# akabeacon_circle_MDBT40_type2.net
KiCad netlist of a schematic drawn in EAGLE
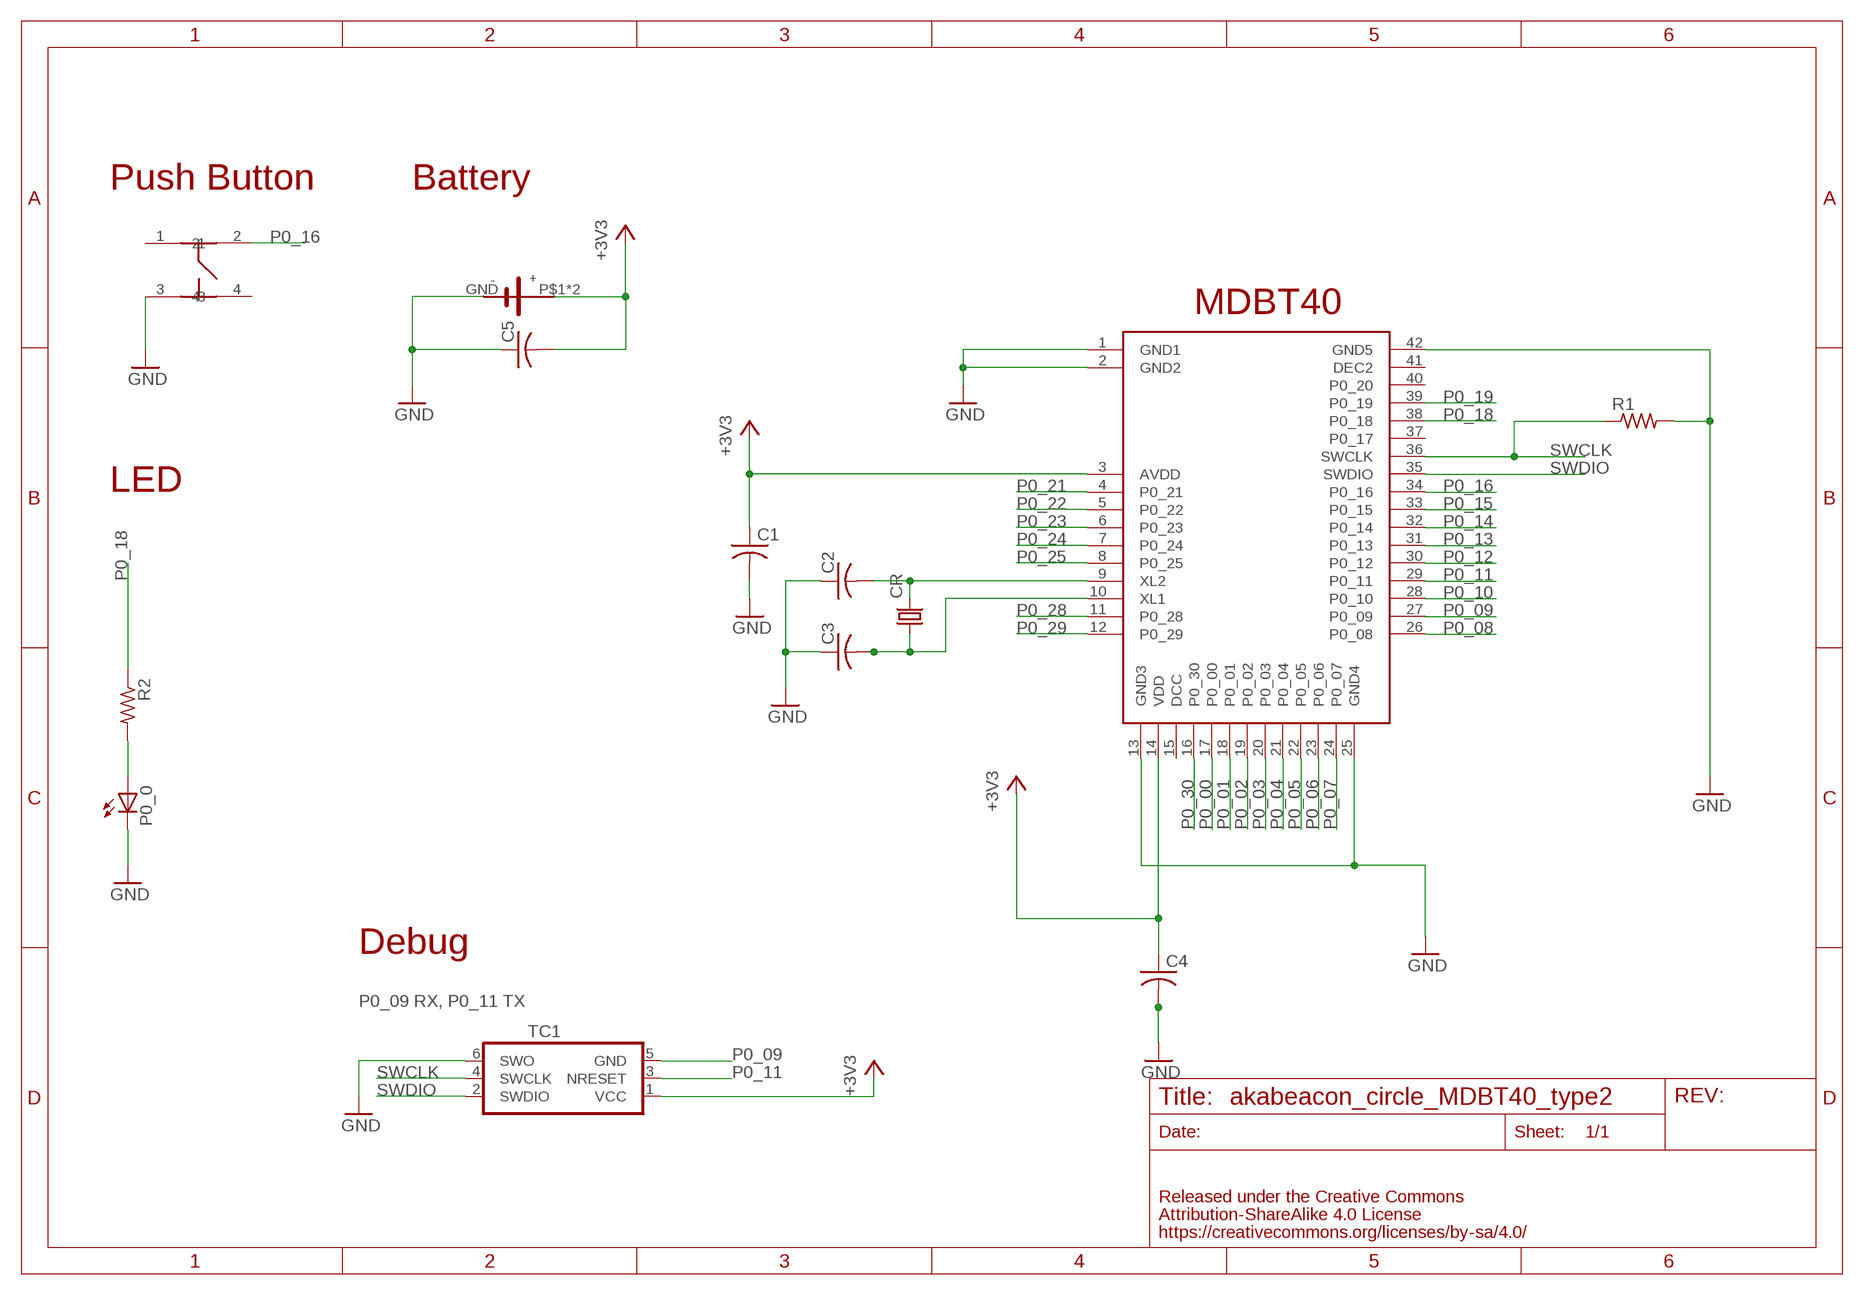
[diagram p0: schematic, sheet 1]

(export (version "E")
  (design (tool "Eeschema 10.0.6"))
  (components
    (comp (ref "C1")
      (value "C-USC0603")
      (footprint "eagle-import:C0603")
      (libsource (lib "eagle-import") (part "C-USC0603"))
    )
    (comp (ref "C2")
      (value "C-USC0603")
      (footprint "eagle-import:C0603")
      (libsource (lib "eagle-import") (part "C-USC0603"))
    )
    (comp (ref "C3")
      (value "C-USC0603")
      (footprint "eagle-import:C0603")
      (libsource (lib "eagle-import") (part "C-USC0603"))
    )
    (comp (ref "C4")
      (value "C-USC0603")
      (footprint "eagle-import:C0603")
      (libsource (lib "eagle-import") (part "C-USC0603"))
    )
    (comp (ref "C5")
      (value "C-USC0603")
      (footprint "eagle-import:C0603")
      (libsource (lib "eagle-import") (part "C-USC0603"))
    )
    (comp (ref "CR")
      (value "FC-12M")
      (footprint "eagle-import:FC-12M")
      (libsource (lib "eagle-import") (part "FC-12M"))
    )
    (comp (ref "P0_0")
      (value "LEDCHIP-LED0603")
      (footprint "eagle-import:CHIP-LED0603")
      (libsource (lib "eagle-import") (part "LEDCHIP-LED0603"))
    )
    (comp (ref "R1")
      (value "R-US_R0603")
      (footprint "eagle-import:R0603")
      (libsource (lib "eagle-import") (part "R-US_R0603"))
    )
    (comp (ref "R2")
      (value "R-US_R0603")
      (footprint "eagle-import:R0603")
      (libsource (lib "eagle-import") (part "R-US_R0603"))
    )
    (comp (ref "TC1")
      (value "TC2030-IDC-NL")
      (footprint "eagle-import:TC2030-IDC-NL")
      (libsource (lib "eagle-import") (part "TC2030-IDC-NL"))
    )
    (comp (ref "U$1")
      (value "RAYTAC-MDBT40")
      (footprint "eagle-import:RAYTAC-MDBT40")
      (libsource (lib "eagle-import") (part "RAYTAC-MDBT40"))
    )
    (comp (ref "U$3")
      (value "CIRCLE-TYPE2")
      (footprint "eagle-import:CIRCLE-TYPE2-TC2030")
      (libsource (lib "eagle-import") (part "CIRCLE-TYPE2"))
    )
    (comp (ref "U$5")
      (value "SWICTH-4P(KMR2)")
      (footprint "eagle-import:SWITCH-4P(KMR2)")
      (libsource (lib "eagle-import") (part "SWICTH-4P(KMR2)"))
    )
  )
  (nets
    (net (code "1") (name "+3V3") (class "Default")
      (node (ref "C1") (pin "1") (pinfunction "1_1") (pintype "passive"))
      (node (ref "C4") (pin "1") (pinfunction "1_1") (pintype "passive"))
      (node (ref "C5") (pin "2") (pinfunction "2_2") (pintype "passive"))
      (node (ref "TC1") (pin "1") (pinfunction "VCC_1") (pintype "passive"))
      (node (ref "U$1") (pin "14") (pinfunction "VDD_14") (pintype "bidirectional"))
      (node (ref "U$1") (pin "3") (pinfunction "AVDD_3") (pintype "bidirectional"))
      (node (ref "U$3") (pin "P$1") (pinfunction "VCC_P$1") (pintype "bidirectional"))
      (node (ref "U$3") (pin "P$2") (pinfunction "VCC_P$2") (pintype "bidirectional"))
    )
    (net (code "2") (name "/P0_00") (class "Default")
      (node (ref "U$1") (pin "17") (pinfunction "P0_00_17") (pintype "bidirectional"))
    )
    (net (code "3") (name "/P0_01") (class "Default")
      (node (ref "U$1") (pin "18") (pinfunction "P0_01_18") (pintype "bidirectional"))
    )
    (net (code "4") (name "/P0_02") (class "Default")
      (node (ref "U$1") (pin "19") (pinfunction "P0_02_19") (pintype "bidirectional"))
    )
    (net (code "5") (name "/P0_03") (class "Default")
      (node (ref "U$1") (pin "20") (pinfunction "P0_03_20") (pintype "bidirectional"))
    )
    (net (code "6") (name "/P0_04") (class "Default")
      (node (ref "U$1") (pin "21") (pinfunction "P0_04_21") (pintype "bidirectional"))
    )
    (net (code "7") (name "/P0_05") (class "Default")
      (node (ref "U$1") (pin "22") (pinfunction "P0_05_22") (pintype "bidirectional"))
    )
    (net (code "8") (name "/P0_06") (class "Default")
      (node (ref "U$1") (pin "23") (pinfunction "P0_06_23") (pintype "bidirectional"))
    )
    (net (code "9") (name "/P0_07") (class "Default")
      (node (ref "U$1") (pin "24") (pinfunction "P0_07_24") (pintype "bidirectional"))
    )
    (net (code "10") (name "/P0_08") (class "Default")
      (node (ref "U$1") (pin "26") (pinfunction "P0_08_26") (pintype "bidirectional"))
    )
    (net (code "11") (name "/P0_09") (class "Default")
      (node (ref "TC1") (pin "5") (pinfunction "GND_5") (pintype "passive"))
      (node (ref "U$1") (pin "27") (pinfunction "P0_09_27") (pintype "bidirectional"))
    )
    (net (code "12") (name "/P0_10") (class "Default")
      (node (ref "U$1") (pin "28") (pinfunction "P0_10_28") (pintype "bidirectional"))
    )
    (net (code "13") (name "/P0_11") (class "Default")
      (node (ref "TC1") (pin "3") (pinfunction "NRESET_3") (pintype "passive"))
      (node (ref "U$1") (pin "29") (pinfunction "P0_11_29") (pintype "bidirectional"))
    )
    (net (code "14") (name "/P0_12") (class "Default")
      (node (ref "U$1") (pin "30") (pinfunction "P0_12_30") (pintype "bidirectional"))
    )
    (net (code "15") (name "/P0_13") (class "Default")
      (node (ref "U$1") (pin "31") (pinfunction "P0_13_31") (pintype "bidirectional"))
    )
    (net (code "16") (name "/P0_14") (class "Default")
      (node (ref "U$1") (pin "32") (pinfunction "P0_14_32") (pintype "bidirectional"))
    )
    (net (code "17") (name "/P0_15") (class "Default")
      (node (ref "U$1") (pin "33") (pinfunction "P0_15_33") (pintype "bidirectional"))
    )
    (net (code "18") (name "/P0_16") (class "Default")
      (node (ref "U$1") (pin "34") (pinfunction "P0_16_34") (pintype "bidirectional"))
      (node (ref "U$5") (pin "2") (pinfunction "2_2") (pintype "bidirectional"))
    )
    (net (code "19") (name "/P0_18") (class "Default")
      (node (ref "R2") (pin "1") (pinfunction "1_1") (pintype "passive"))
      (node (ref "U$1") (pin "38") (pinfunction "P0_18_38") (pintype "bidirectional"))
    )
    (net (code "20") (name "/P0_19") (class "Default")
      (node (ref "U$1") (pin "39") (pinfunction "P0_19_39") (pintype "bidirectional"))
    )
    (net (code "21") (name "/P0_21") (class "Default")
      (node (ref "U$1") (pin "4") (pinfunction "P0_21_4") (pintype "bidirectional"))
    )
    (net (code "22") (name "/P0_22") (class "Default")
      (node (ref "U$1") (pin "5") (pinfunction "P0_22_5") (pintype "bidirectional"))
    )
    (net (code "23") (name "/P0_23") (class "Default")
      (node (ref "U$1") (pin "6") (pinfunction "P0_23_6") (pintype "bidirectional"))
    )
    (net (code "24") (name "/P0_24") (class "Default")
      (node (ref "U$1") (pin "7") (pinfunction "P0_24_7") (pintype "bidirectional"))
    )
    (net (code "25") (name "/P0_25") (class "Default")
      (node (ref "U$1") (pin "8") (pinfunction "P0_25_8") (pintype "bidirectional"))
    )
    (net (code "26") (name "/P0_28") (class "Default")
      (node (ref "U$1") (pin "11") (pinfunction "P0_28_11") (pintype "bidirectional"))
    )
    (net (code "27") (name "/P0_29") (class "Default")
      (node (ref "U$1") (pin "12") (pinfunction "P0_29_12") (pintype "bidirectional"))
    )
    (net (code "28") (name "/P0_30") (class "Default")
      (node (ref "U$1") (pin "16") (pinfunction "P0_30_16") (pintype "bidirectional"))
    )
    (net (code "29") (name "/SWCLK") (class "Default")
      (node (ref "R1") (pin "1") (pinfunction "1_1") (pintype "passive"))
      (node (ref "TC1") (pin "4") (pinfunction "SWCLK_4") (pintype "passive"))
      (node (ref "U$1") (pin "36") (pinfunction "SWCLK_36") (pintype "bidirectional"))
    )
    (net (code "30") (name "/SWDIO") (class "Default")
      (node (ref "TC1") (pin "2") (pinfunction "SWDIO_2") (pintype "passive"))
      (node (ref "U$1") (pin "35") (pinfunction "SWDIO_35") (pintype "bidirectional"))
    )
    (net (code "31") (name "GND") (class "Default")
      (node (ref "C1") (pin "2") (pinfunction "2_2") (pintype "passive"))
      (node (ref "C2") (pin "1") (pinfunction "1_1") (pintype "passive"))
      (node (ref "C3") (pin "1") (pinfunction "1_1") (pintype "passive"))
      (node (ref "C4") (pin "2") (pinfunction "2_2") (pintype "passive"))
      (node (ref "C5") (pin "1") (pinfunction "1_1") (pintype "passive"))
      (node (ref "P0_0") (pin "C") (pinfunction "C_C") (pintype "passive"))
      (node (ref "R1") (pin "2") (pinfunction "2_2") (pintype "passive"))
      (node (ref "TC1") (pin "6") (pinfunction "SWO_6") (pintype "passive"))
      (node (ref "U$1") (pin "1") (pinfunction "GND1_1") (pintype "bidirectional"))
      (node (ref "U$1") (pin "13") (pinfunction "GND3_13") (pintype "bidirectional"))
      (node (ref "U$1") (pin "2") (pinfunction "GND2_2") (pintype "bidirectional"))
      (node (ref "U$1") (pin "25") (pinfunction "GND4_25") (pintype "bidirectional"))
      (node (ref "U$1") (pin "42") (pinfunction "GND5_42") (pintype "bidirectional"))
      (node (ref "U$3") (pin "GND") (pinfunction "GND_GND") (pintype "bidirectional"))
      (node (ref "U$5") (pin "3") (pinfunction "3_3") (pintype "bidirectional"))
    )
    (net (code "32") (name "Net-(P0_0-PadA)") (class "Default")
      (node (ref "P0_0") (pin "A") (pinfunction "A_A") (pintype "passive"))
      (node (ref "R2") (pin "2") (pinfunction "2_2") (pintype "passive"))
    )
    (net (code "33") (name "Net-(U$1-XL1)") (class "Default")
      (node (ref "C3") (pin "2") (pinfunction "2_2") (pintype "passive"))
      (node (ref "CR") (pin "1") (pinfunction "1_1") (pintype "passive"))
      (node (ref "U$1") (pin "10") (pinfunction "XL1_10") (pintype "bidirectional"))
    )
    (net (code "34") (name "Net-(U$1-XL2)") (class "Default")
      (node (ref "C2") (pin "2") (pinfunction "2_2") (pintype "passive"))
      (node (ref "CR") (pin "2") (pinfunction "2_2") (pintype "passive"))
      (node (ref "U$1") (pin "9") (pinfunction "XL2_9") (pintype "bidirectional"))
    )
    (net (code "35") (name "unconnected-(U$1-DCC-Pad15)") (class "Default")
      (node (ref "U$1") (pin "15") (pinfunction "DCC_15") (pintype "bidirectional"))
    )
    (net (code "36") (name "unconnected-(U$1-DEC2-Pad41)") (class "Default")
      (node (ref "U$1") (pin "41") (pinfunction "DEC2_41") (pintype "bidirectional"))
    )
    (net (code "37") (name "unconnected-(U$1-P0_17-Pad37)") (class "Default")
      (node (ref "U$1") (pin "37") (pinfunction "P0_17_37") (pintype "bidirectional"))
    )
    (net (code "38") (name "unconnected-(U$1-P0_20-Pad40)") (class "Default")
      (node (ref "U$1") (pin "40") (pinfunction "P0_20_40") (pintype "bidirectional"))
    )
    (net (code "39") (name "unconnected-(U$5-Pad1)") (class "Default")
      (node (ref "U$5") (pin "1") (pinfunction "1_1") (pintype "bidirectional"))
    )
    (net (code "40") (name "unconnected-(U$5-Pad4)") (class "Default")
      (node (ref "U$5") (pin "4") (pinfunction "4_4") (pintype "bidirectional"))
    )
  )
)
